# vacuum-controller-rev-a.net
KiCad netlist of a schematic drawn in EAGLE
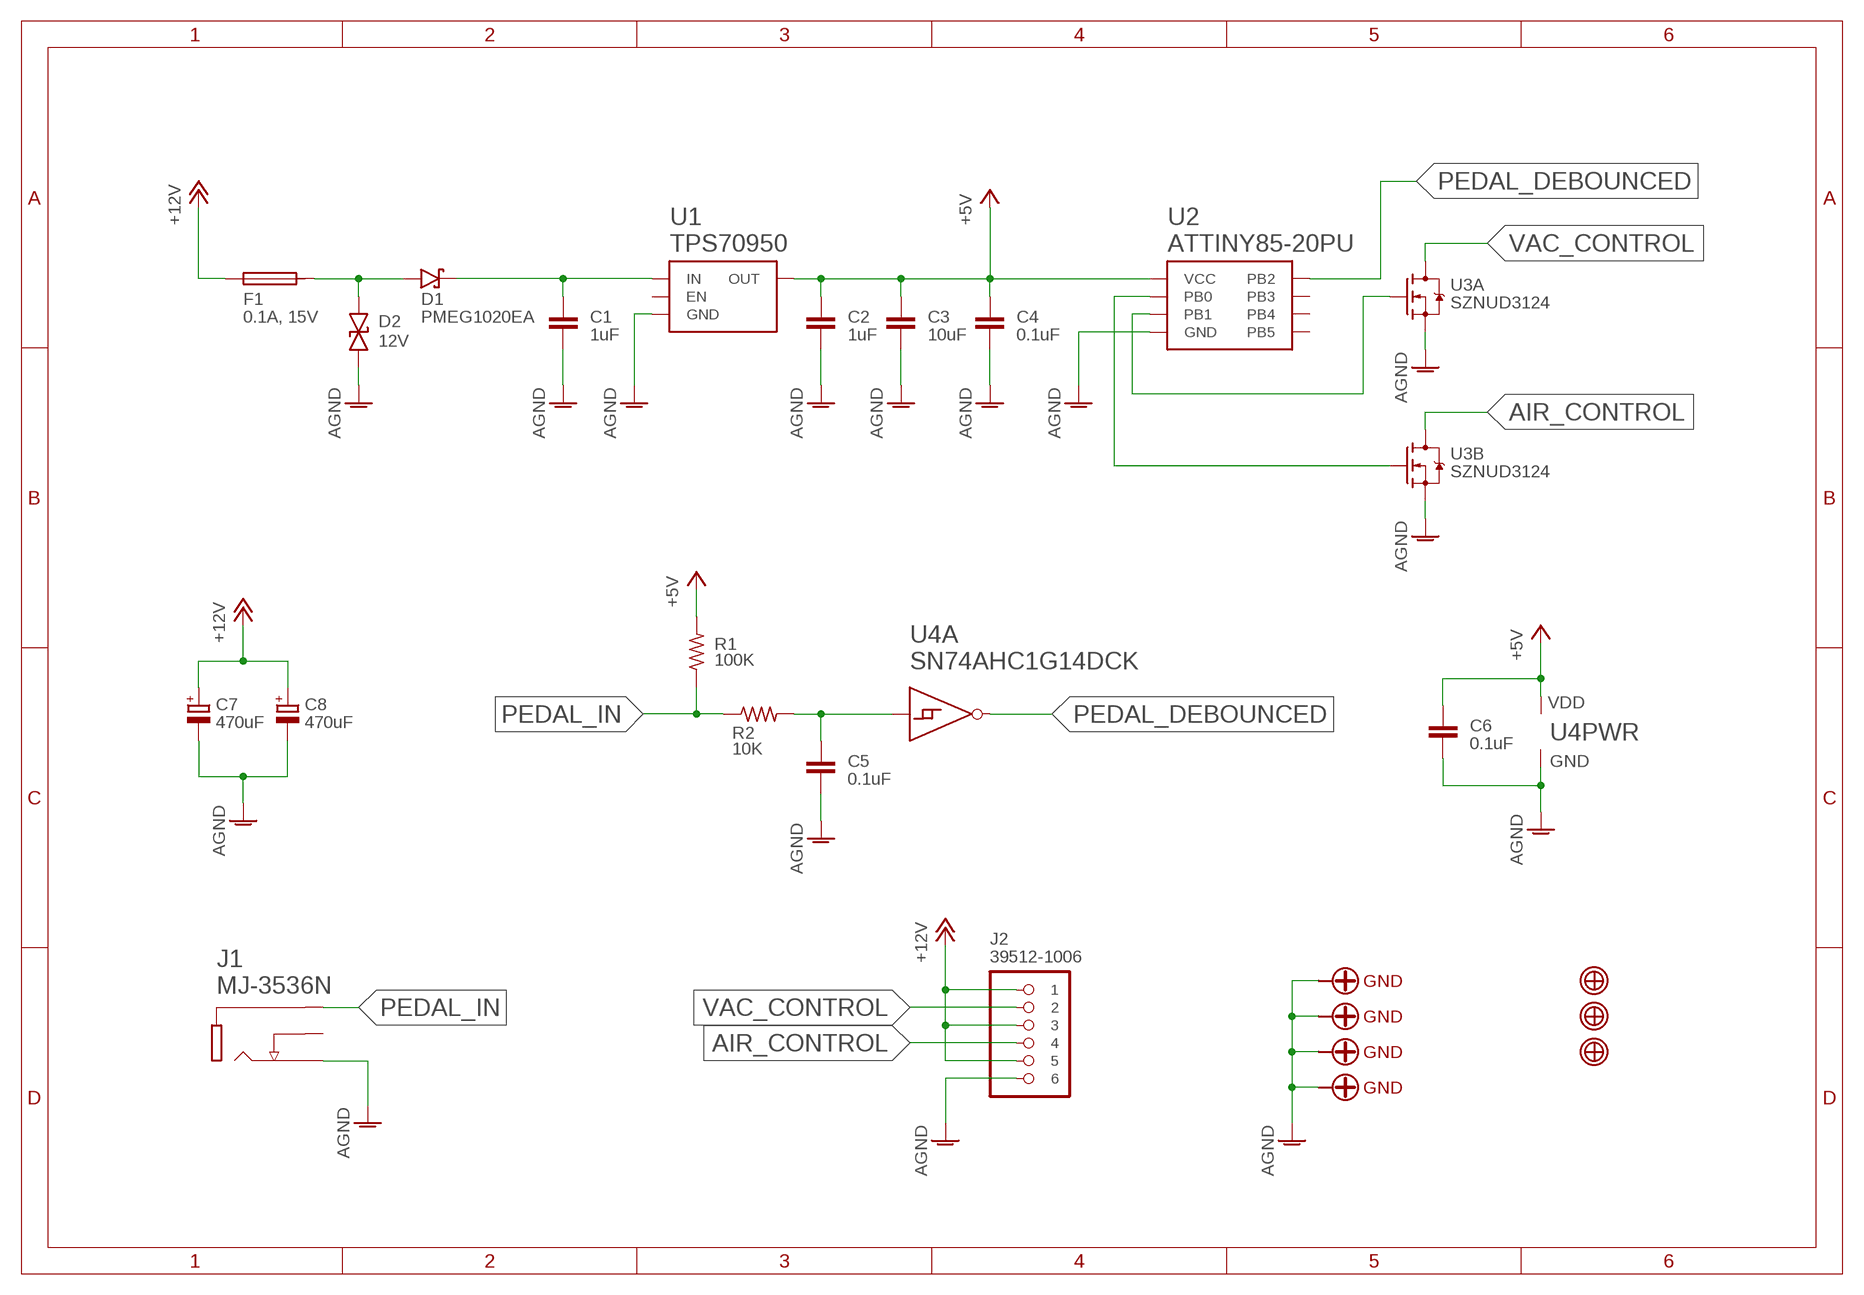
[diagram p0: schematic, sheet 1]

(export (version "E")
  (design (tool "Eeschema 10.0.6"))
  (components
    (comp (ref "C1")
      (value "1uF")
      (footprint "eagle-import:C0603")
      (libsource (lib "eagle-import") (part "CAPACITOR-0603"))
    )
    (comp (ref "C2")
      (value "1uF")
      (footprint "eagle-import:C0603")
      (libsource (lib "eagle-import") (part "CAPACITOR-0603"))
    )
    (comp (ref "C3")
      (value "10uF")
      (footprint "eagle-import:C0805")
      (libsource (lib "eagle-import") (part "CAPACITOR-0805"))
    )
    (comp (ref "C4")
      (value "0.1uF")
      (footprint "eagle-import:C0402")
      (libsource (lib "eagle-import") (part "CAPACITOR-0402"))
    )
    (comp (ref "C5")
      (value "0.1uF")
      (footprint "eagle-import:C0402")
      (libsource (lib "eagle-import") (part "CAPACITOR-0402"))
    )
    (comp (ref "C6")
      (value "0.1uF")
      (footprint "eagle-import:C0402")
      (libsource (lib "eagle-import") (part "CAPACITOR-0402"))
    )
    (comp (ref "C7")
      (value "470uF")
      (footprint "eagle-import:RADIAL-D8-P3.5-PD0.5")
      (libsource (lib "eagle-import") (part "CAPACITOR-POLARIZED-RADIAL-D8-P3.5-PD0.5"))
    )
    (comp (ref "C8")
      (value "470uF")
      (footprint "eagle-import:RADIAL-D8-P3.5-PD0.5")
      (libsource (lib "eagle-import") (part "CAPACITOR-POLARIZED-RADIAL-D8-P3.5-PD0.5"))
    )
    (comp (ref "D1")
      (value "PMEG1020EA")
      (footprint "eagle-import:SOD323-R")
      (libsource (lib "eagle-import") (part "PMEG1020EA"))
    )
    (comp (ref "D2")
      (value "12V")
      (footprint "eagle-import:SMA")
      (libsource (lib "eagle-import") (part "SUPPRESSOR-DUAL-SMA"))
    )
    (comp (ref "F1")
      (value "0.1A, 15V")
      (footprint "eagle-import:C0805")
      (libsource (lib "eagle-import") (part "FUSE-HORIZONTAL-0805"))
    )
    (comp (ref "J1")
      (value "MJ-3536N")
      (footprint "eagle-import:MJ-3536N")
      (libsource (lib "eagle-import") (part "MJ-3536N"))
    )
    (comp (ref "J2")
      (value "39512-1006")
      (footprint "eagle-import:39512-1006")
      (libsource (lib "eagle-import") (part "39512-1006"))
    )
    (comp (ref "R1")
      (value "100K")
      (footprint "eagle-import:R0402")
      (libsource (lib "eagle-import") (part "RESISTOR-0402"))
    )
    (comp (ref "R2")
      (value "10K")
      (footprint "eagle-import:R0402")
      (libsource (lib "eagle-import") (part "RESISTOR-HORIZONTAL-0402"))
    )
    (comp (ref "U$1")
      (value "SCREW-THRU-GND-#4")
      (footprint "eagle-import:SCREW-THRU-GND-#4")
      (libsource (lib "eagle-import") (part "SCREW-THRU-GND-#4"))
    )
    (comp (ref "U$2")
      (value "SCREW-THRU-GND-#4")
      (footprint "eagle-import:SCREW-THRU-GND-#4")
      (libsource (lib "eagle-import") (part "SCREW-THRU-GND-#4"))
    )
    (comp (ref "U$3")
      (value "SCREW-THRU-GND-#4")
      (footprint "eagle-import:SCREW-THRU-GND-#4")
      (libsource (lib "eagle-import") (part "SCREW-THRU-GND-#4"))
    )
    (comp (ref "U$4")
      (value "SCREW-THRU-GND-#4")
      (footprint "eagle-import:SCREW-THRU-GND-#4")
      (libsource (lib "eagle-import") (part "SCREW-THRU-GND-#4"))
    )
    (comp (ref "U$5")
      (value "FIDUCIAL-1MM")
      (footprint "eagle-import:FIDUCIAL_1MM")
      (libsource (lib "eagle-import") (part "FIDUCIAL-1MM"))
    )
    (comp (ref "U$6")
      (value "FIDUCIAL-1MM")
      (footprint "eagle-import:FIDUCIAL_1MM")
      (libsource (lib "eagle-import") (part "FIDUCIAL-1MM"))
    )
    (comp (ref "U$7")
      (value "FIDUCIAL-1MM")
      (footprint "eagle-import:FIDUCIAL_1MM")
      (libsource (lib "eagle-import") (part "FIDUCIAL-1MM"))
    )
    (comp (ref "U1")
      (value "TPS70950")
      (footprint "eagle-import:R-PDSO-G5-DBV")
      (libsource (lib "eagle-import") (part "TPS709"))
    )
    (comp (ref "U2")
      (value "ATTINY85-20PU")
      (footprint "eagle-import:PDIP-8")
      (libsource (lib "eagle-import") (part "ATTINY85-20PU"))
    )
    (comp (ref "U3")
      (value "SZNUD3124")
      (footprint "eagle-import:SOT-457")
      (fields (field (name "PN") "SZNUD3124DMT1G"))
      (libsource (lib "eagle-import") (part "SZNUD3124"))
    )
    (comp (ref "U4")
      (value "SN74AHC1G14DCK")
      (footprint "eagle-import:R-PDSO-G5-DCK")
      (fields (field (name "PN") "SN74AHC1G14DCKR"))
      (libsource (lib "eagle-import") (part "SN74AHC1G14DCK"))
    )
  )
  (nets
    (net (code "1") (name "+5V") (class "Default")
      (node (ref "C2") (pin "1") (pinfunction "1_1") (pintype "passive"))
      (node (ref "C3") (pin "1") (pinfunction "1_1") (pintype "passive"))
      (node (ref "C4") (pin "1") (pinfunction "1_1") (pintype "passive"))
      (node (ref "C6") (pin "1") (pinfunction "1_1") (pintype "passive"))
      (node (ref "R1") (pin "2") (pinfunction "2_2") (pintype "passive"))
      (node (ref "U1") (pin "5") (pinfunction "OUT_5") (pintype "bidirectional"))
      (node (ref "U2") (pin "P$8") (pinfunction "VCC_P$8") (pintype "bidirectional"))
      (node (ref "U4") (pin "5") (pinfunction "VDD_5") (pintype "bidirectional"))
    )
    (net (code "2") (name "+12V") (class "Default")
      (node (ref "C7") (pin "+") (pinfunction "+_+") (pintype "passive"))
      (node (ref "C8") (pin "+") (pinfunction "+_+") (pintype "passive"))
      (node (ref "F1") (pin "1") (pinfunction "1_1") (pintype "passive"))
      (node (ref "J2") (pin "P$1") (pinfunction "1_P$1") (pintype "bidirectional"))
      (node (ref "J2") (pin "P$3") (pinfunction "3_P$3") (pintype "bidirectional"))
      (node (ref "J2") (pin "P$5") (pinfunction "5_P$5") (pintype "bidirectional"))
    )
    (net (code "3") (name "AGND") (class "Default")
      (node (ref "C1") (pin "2") (pinfunction "2_2") (pintype "passive"))
      (node (ref "C2") (pin "2") (pinfunction "2_2") (pintype "passive"))
      (node (ref "C3") (pin "2") (pinfunction "2_2") (pintype "passive"))
      (node (ref "C4") (pin "2") (pinfunction "2_2") (pintype "passive"))
      (node (ref "C5") (pin "2") (pinfunction "2_2") (pintype "passive"))
      (node (ref "C6") (pin "2") (pinfunction "2_2") (pintype "passive"))
      (node (ref "C7") (pin "-") (pinfunction "-_-") (pintype "passive"))
      (node (ref "C8") (pin "-") (pinfunction "-_-") (pintype "passive"))
      (node (ref "D2") (pin "A") (pinfunction "A_A") (pintype "passive"))
      (node (ref "J1") (pin "P$2") (pinfunction "P$3_P$2") (pintype "bidirectional"))
      (node (ref "J2") (pin "P$6") (pinfunction "6_P$6") (pintype "bidirectional"))
      (node (ref "U$1") (pin "P$1") (pinfunction "GND_P$1") (pintype "power_in"))
      (node (ref "U$1") (pin "P$2") (pinfunction "GND_P$2") (pintype "power_in"))
      (node (ref "U$1") (pin "P$3") (pinfunction "GND_P$3") (pintype "power_in"))
      (node (ref "U$1") (pin "P$4") (pinfunction "GND_P$4") (pintype "power_in"))
      (node (ref "U$1") (pin "P$5") (pinfunction "GND_P$5") (pintype "power_in"))
      (node (ref "U$1") (pin "P$6") (pinfunction "GND_P$6") (pintype "power_in"))
      (node (ref "U$1") (pin "P$7") (pinfunction "GND_P$7") (pintype "power_in"))
      (node (ref "U$1") (pin "P$8") (pinfunction "GND_P$8") (pintype "power_in"))
      (node (ref "U$1") (pin "P$9") (pinfunction "GND_P$9") (pintype "power_in"))
      (node (ref "U$2") (pin "P$1") (pinfunction "GND_P$1") (pintype "power_in"))
      (node (ref "U$2") (pin "P$2") (pinfunction "GND_P$2") (pintype "power_in"))
      (node (ref "U$2") (pin "P$3") (pinfunction "GND_P$3") (pintype "power_in"))
      (node (ref "U$2") (pin "P$4") (pinfunction "GND_P$4") (pintype "power_in"))
      (node (ref "U$2") (pin "P$5") (pinfunction "GND_P$5") (pintype "power_in"))
      (node (ref "U$2") (pin "P$6") (pinfunction "GND_P$6") (pintype "power_in"))
      (node (ref "U$2") (pin "P$7") (pinfunction "GND_P$7") (pintype "power_in"))
      (node (ref "U$2") (pin "P$8") (pinfunction "GND_P$8") (pintype "power_in"))
      (node (ref "U$2") (pin "P$9") (pinfunction "GND_P$9") (pintype "power_in"))
      (node (ref "U$3") (pin "P$1") (pinfunction "GND_P$1") (pintype "power_in"))
      (node (ref "U$3") (pin "P$2") (pinfunction "GND_P$2") (pintype "power_in"))
      (node (ref "U$3") (pin "P$3") (pinfunction "GND_P$3") (pintype "power_in"))
      (node (ref "U$3") (pin "P$4") (pinfunction "GND_P$4") (pintype "power_in"))
      (node (ref "U$3") (pin "P$5") (pinfunction "GND_P$5") (pintype "power_in"))
      (node (ref "U$3") (pin "P$6") (pinfunction "GND_P$6") (pintype "power_in"))
      (node (ref "U$3") (pin "P$7") (pinfunction "GND_P$7") (pintype "power_in"))
      (node (ref "U$3") (pin "P$8") (pinfunction "GND_P$8") (pintype "power_in"))
      (node (ref "U$3") (pin "P$9") (pinfunction "GND_P$9") (pintype "power_in"))
      (node (ref "U$4") (pin "P$1") (pinfunction "GND_P$1") (pintype "power_in"))
      (node (ref "U$4") (pin "P$2") (pinfunction "GND_P$2") (pintype "power_in"))
      (node (ref "U$4") (pin "P$3") (pinfunction "GND_P$3") (pintype "power_in"))
      (node (ref "U$4") (pin "P$4") (pinfunction "GND_P$4") (pintype "power_in"))
      (node (ref "U$4") (pin "P$5") (pinfunction "GND_P$5") (pintype "power_in"))
      (node (ref "U$4") (pin "P$6") (pinfunction "GND_P$6") (pintype "power_in"))
      (node (ref "U$4") (pin "P$7") (pinfunction "GND_P$7") (pintype "power_in"))
      (node (ref "U$4") (pin "P$8") (pinfunction "GND_P$8") (pintype "power_in"))
      (node (ref "U$4") (pin "P$9") (pinfunction "GND_P$9") (pintype "power_in"))
      (node (ref "U1") (pin "2") (pinfunction "GND_2") (pintype "bidirectional"))
      (node (ref "U2") (pin "P$4") (pinfunction "GND_P$4") (pintype "bidirectional"))
      (node (ref "U3") (pin "1") (pinfunction "S_1") (pintype "passive"))
      (node (ref "U3") (pin "4") (pinfunction "S_4") (pintype "passive"))
      (node (ref "U4") (pin "3") (pinfunction "GND_3") (pintype "bidirectional"))
    )
    (net (code "4") (name "AIR_CONTROL") (class "Default")
      (node (ref "J2") (pin "P$4") (pinfunction "4_P$4") (pintype "bidirectional"))
      (node (ref "U3") (pin "3") (pinfunction "D_3") (pintype "passive"))
    )
    (net (code "5") (name "Net-(D1-PadA)") (class "Default")
      (node (ref "D1") (pin "A") (pinfunction "A_A") (pintype "passive"))
      (node (ref "D2") (pin "C") (pinfunction "C_C") (pintype "passive"))
      (node (ref "F1") (pin "2") (pinfunction "2_2") (pintype "passive"))
    )
    (net (code "6") (name "Net-(U1-IN)") (class "Default")
      (node (ref "C1") (pin "1") (pinfunction "1_1") (pintype "passive"))
      (node (ref "D1") (pin "C") (pinfunction "C_C") (pintype "passive"))
      (node (ref "U1") (pin "1") (pinfunction "IN_1") (pintype "bidirectional"))
    )
    (net (code "7") (name "Net-(U2-PB0)") (class "Default")
      (node (ref "U2") (pin "P$5") (pinfunction "PB0_P$5") (pintype "bidirectional"))
      (node (ref "U3") (pin "5") (pinfunction "G_5") (pintype "passive"))
    )
    (net (code "8") (name "Net-(U2-PB1)") (class "Default")
      (node (ref "U2") (pin "P$6") (pinfunction "PB1_P$6") (pintype "bidirectional"))
      (node (ref "U3") (pin "2") (pinfunction "G_2") (pintype "passive"))
    )
    (net (code "9") (name "Net-(U4A-A)") (class "Default")
      (node (ref "C5") (pin "1") (pinfunction "1_1") (pintype "passive"))
      (node (ref "R2") (pin "2") (pinfunction "2_2") (pintype "passive"))
      (node (ref "U4") (pin "2") (pinfunction "A_2") (pintype "input"))
    )
    (net (code "10") (name "PEDAL_DEBOUNCED") (class "Default")
      (node (ref "U2") (pin "P$7") (pinfunction "PB2_P$7") (pintype "bidirectional"))
      (node (ref "U4") (pin "4") (pinfunction "Y_4") (pintype "output"))
    )
    (net (code "11") (name "PEDAL_IN") (class "Default")
      (node (ref "J1") (pin "P$1") (pinfunction "P$1_P$1") (pintype "bidirectional"))
      (node (ref "R1") (pin "1") (pinfunction "1_1") (pintype "passive"))
      (node (ref "R2") (pin "1") (pinfunction "1_1") (pintype "passive"))
    )
    (net (code "12") (name "VAC_CONTROL") (class "Default")
      (node (ref "J2") (pin "P$2") (pinfunction "2_P$2") (pintype "bidirectional"))
      (node (ref "U3") (pin "6") (pinfunction "D_6") (pintype "passive"))
    )
    (net (code "13") (name "unconnected-(J1-P$2-PadP$3)") (class "Default")
      (node (ref "J1") (pin "P$3") (pinfunction "P$2_P$3") (pintype "bidirectional"))
    )
    (net (code "14") (name "unconnected-(U1-EN-Pad3)") (class "Default")
      (node (ref "U1") (pin "3") (pinfunction "EN_3") (pintype "bidirectional"))
    )
    (net (code "15") (name "unconnected-(U2-PB3-PadP$2)") (class "Default")
      (node (ref "U2") (pin "P$2") (pinfunction "PB3_P$2") (pintype "bidirectional"))
    )
    (net (code "16") (name "unconnected-(U2-PB4-PadP$3)") (class "Default")
      (node (ref "U2") (pin "P$3") (pinfunction "PB4_P$3") (pintype "bidirectional"))
    )
    (net (code "17") (name "unconnected-(U2-PB5-PadP$1)") (class "Default")
      (node (ref "U2") (pin "P$1") (pinfunction "PB5_P$1") (pintype "bidirectional"))
    )
  )
)
